# LM358_VCO_smd.net
KiCad netlist of a schematic drawn in EAGLE
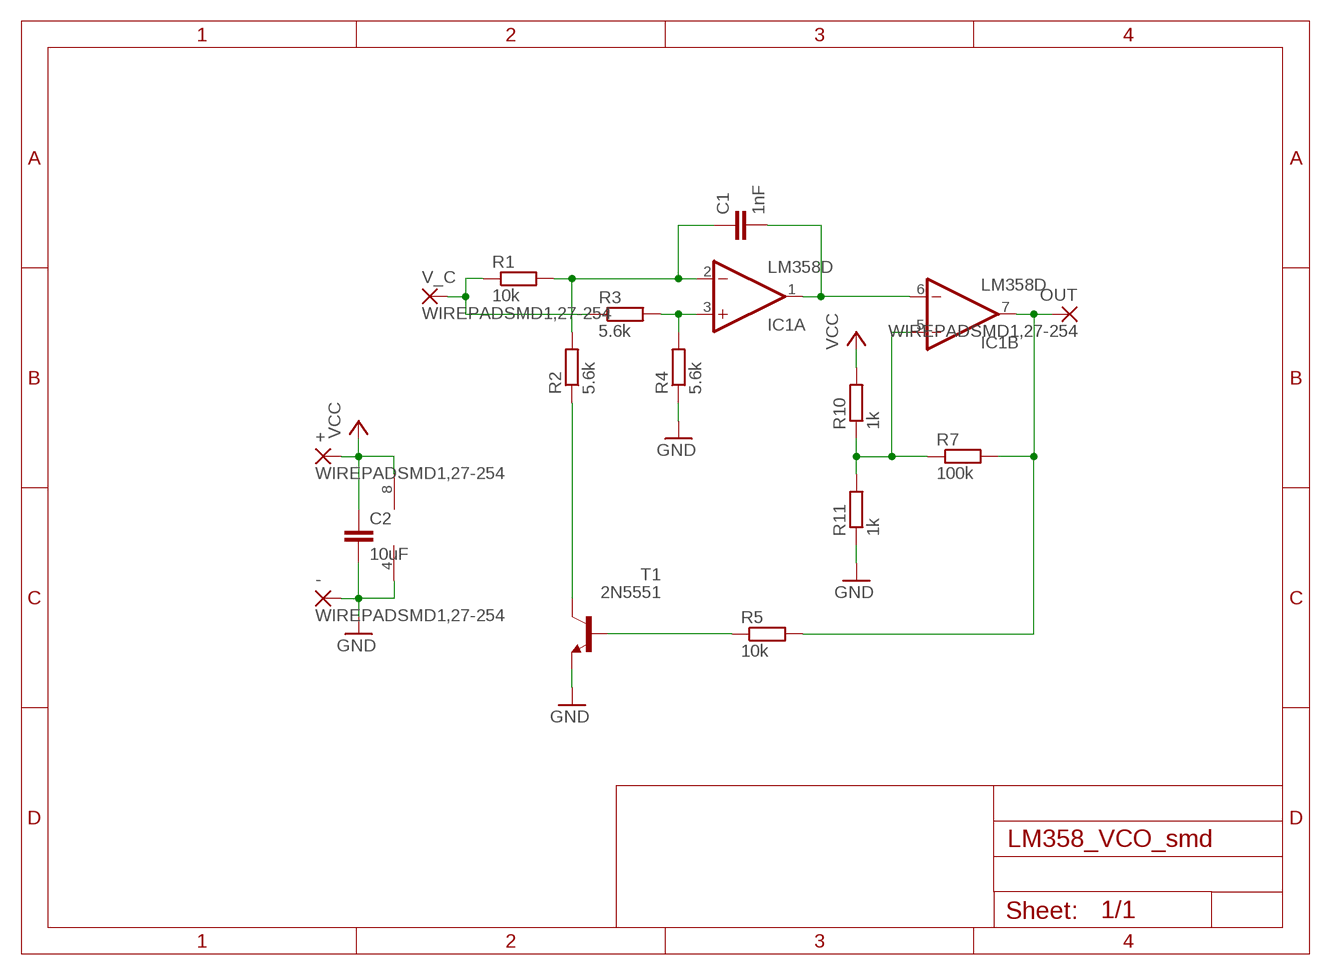
[diagram p0: schematic, sheet 1]

(export (version "E")
  (design (tool "Eeschema 10.0.6"))
  (components
    (comp (ref "+")
      (value "WIREPADSMD1,27-254")
      (footprint "eagle-import:SMD1,27-2,54")
      (libsource (lib "eagle-import") (part "WIREPADSMD1,27-254"))
    )
    (comp (ref "-")
      (value "WIREPADSMD1,27-254")
      (footprint "eagle-import:SMD1,27-2,54")
      (libsource (lib "eagle-import") (part "WIREPADSMD1,27-254"))
    )
    (comp (ref "C1")
      (value "1nF")
      (footprint "eagle-import:C0805")
      (libsource (lib "eagle-import") (part "C-EUC0805"))
    )
    (comp (ref "C2")
      (value "10uF")
      (footprint "eagle-import:C0805")
      (libsource (lib "eagle-import") (part "C-EUC0805"))
    )
    (comp (ref "IC1")
      (value "LM358D")
      (footprint "eagle-import:SO08")
      (libsource (lib "eagle-import") (part "LM358D"))
    )
    (comp (ref "OUT")
      (value "WIREPADSMD1,27-254")
      (footprint "eagle-import:SMD1,27-2,54")
      (libsource (lib "eagle-import") (part "WIREPADSMD1,27-254"))
    )
    (comp (ref "R1")
      (value "10k")
      (footprint "eagle-import:R0805")
      (libsource (lib "eagle-import") (part "R-EU_R0805"))
    )
    (comp (ref "R2")
      (value "5.6k")
      (footprint "eagle-import:R0805")
      (libsource (lib "eagle-import") (part "R-EU_R0805"))
    )
    (comp (ref "R3")
      (value "5.6k")
      (footprint "eagle-import:R0805")
      (libsource (lib "eagle-import") (part "R-EU_R0805"))
    )
    (comp (ref "R4")
      (value "5.6k")
      (footprint "eagle-import:R0805")
      (libsource (lib "eagle-import") (part "R-EU_R0805"))
    )
    (comp (ref "R5")
      (value "10k")
      (footprint "eagle-import:R0805")
      (libsource (lib "eagle-import") (part "R-EU_R0805"))
    )
    (comp (ref "R7")
      (value "100k")
      (footprint "eagle-import:R0805")
      (libsource (lib "eagle-import") (part "R-EU_R0805"))
    )
    (comp (ref "R10")
      (value "1k")
      (footprint "eagle-import:R0805")
      (libsource (lib "eagle-import") (part "R-EU_R0805"))
    )
    (comp (ref "R11")
      (value "1k")
      (footprint "eagle-import:R0805")
      (libsource (lib "eagle-import") (part "R-EU_R0805"))
    )
    (comp (ref "T1")
      (value "2N5551")
      (footprint "eagle-import:SOT23-BEC")
      (libsource (lib "eagle-import") (part "-NPN-SOT23-BECMMBT5551LT1"))
    )
    (comp (ref "V_C")
      (value "WIREPADSMD1,27-254")
      (footprint "eagle-import:SMD1,27-2,54")
      (libsource (lib "eagle-import") (part "WIREPADSMD1,27-254"))
    )
  )
  (nets
    (net (code "1") (name "GND") (class "Default")
      (node (ref "-") (pin "1") (pinfunction "P_1") (pintype "passive"))
      (node (ref "C2") (pin "2") (pinfunction "2_2") (pintype "passive"))
      (node (ref "IC1") (pin "4") (pinfunction "V-_4") (pintype "power_in"))
      (node (ref "R11") (pin "1") (pinfunction "1_1") (pintype "passive"))
      (node (ref "R4") (pin "1") (pinfunction "1_1") (pintype "passive"))
      (node (ref "T1") (pin "E") (pinfunction "E_E") (pintype "passive"))
    )
    (net (code "2") (name "Net-(IC1A-+IN)") (class "Default")
      (node (ref "IC1") (pin "3") (pinfunction "+IN_3") (pintype "input"))
      (node (ref "R3") (pin "2") (pinfunction "2_2") (pintype "passive"))
      (node (ref "R4") (pin "2") (pinfunction "2_2") (pintype "passive"))
    )
    (net (code "3") (name "Net-(IC1A--IN)") (class "Default")
      (node (ref "C1") (pin "1") (pinfunction "1_1") (pintype "passive"))
      (node (ref "IC1") (pin "2") (pinfunction "-IN_2") (pintype "input"))
      (node (ref "R1") (pin "2") (pinfunction "2_2") (pintype "passive"))
      (node (ref "R2") (pin "2") (pinfunction "2_2") (pintype "passive"))
    )
    (net (code "4") (name "Net-(IC1A-OUT)") (class "Default")
      (node (ref "C1") (pin "2") (pinfunction "2_2") (pintype "passive"))
      (node (ref "IC1") (pin "1") (pinfunction "OUT_1") (pintype "output"))
      (node (ref "IC1") (pin "6") (pinfunction "-IN_6") (pintype "input"))
    )
    (net (code "5") (name "Net-(IC1B-+IN)") (class "Default")
      (node (ref "IC1") (pin "5") (pinfunction "+IN_5") (pintype "input"))
      (node (ref "R10") (pin "1") (pinfunction "1_1") (pintype "passive"))
      (node (ref "R11") (pin "2") (pinfunction "2_2") (pintype "passive"))
      (node (ref "R7") (pin "1") (pinfunction "1_1") (pintype "passive"))
    )
    (net (code "6") (name "Net-(IC1B-OUT)") (class "Default")
      (node (ref "IC1") (pin "7") (pinfunction "OUT_7") (pintype "output"))
      (node (ref "OUT") (pin "1") (pinfunction "P_1") (pintype "passive"))
      (node (ref "R5") (pin "2") (pinfunction "2_2") (pintype "passive"))
      (node (ref "R7") (pin "2") (pinfunction "2_2") (pintype "passive"))
    )
    (net (code "7") (name "Net-(R2-Pad1)") (class "Default")
      (node (ref "R2") (pin "1") (pinfunction "1_1") (pintype "passive"))
      (node (ref "T1") (pin "C") (pinfunction "C_C") (pintype "passive"))
    )
    (net (code "8") (name "Net-(R5-Pad1)") (class "Default")
      (node (ref "R5") (pin "1") (pinfunction "1_1") (pintype "passive"))
      (node (ref "T1") (pin "B") (pinfunction "B_B") (pintype "passive"))
    )
    (net (code "9") (name "Net-(V_C-P)") (class "Default")
      (node (ref "R1") (pin "1") (pinfunction "1_1") (pintype "passive"))
      (node (ref "R3") (pin "1") (pinfunction "1_1") (pintype "passive"))
      (node (ref "V_C") (pin "1") (pinfunction "P_1") (pintype "passive"))
    )
    (net (code "10") (name "VCC") (class "Default")
      (node (ref "+") (pin "1") (pinfunction "P_1") (pintype "passive"))
      (node (ref "C2") (pin "1") (pinfunction "1_1") (pintype "passive"))
      (node (ref "IC1") (pin "8") (pinfunction "V+_8") (pintype "power_in"))
      (node (ref "R10") (pin "2") (pinfunction "2_2") (pintype "passive"))
    )
  )
)
